# Tic_Tac_Toe_2_0.net
KiCad netlist of a schematic drawn in EAGLE
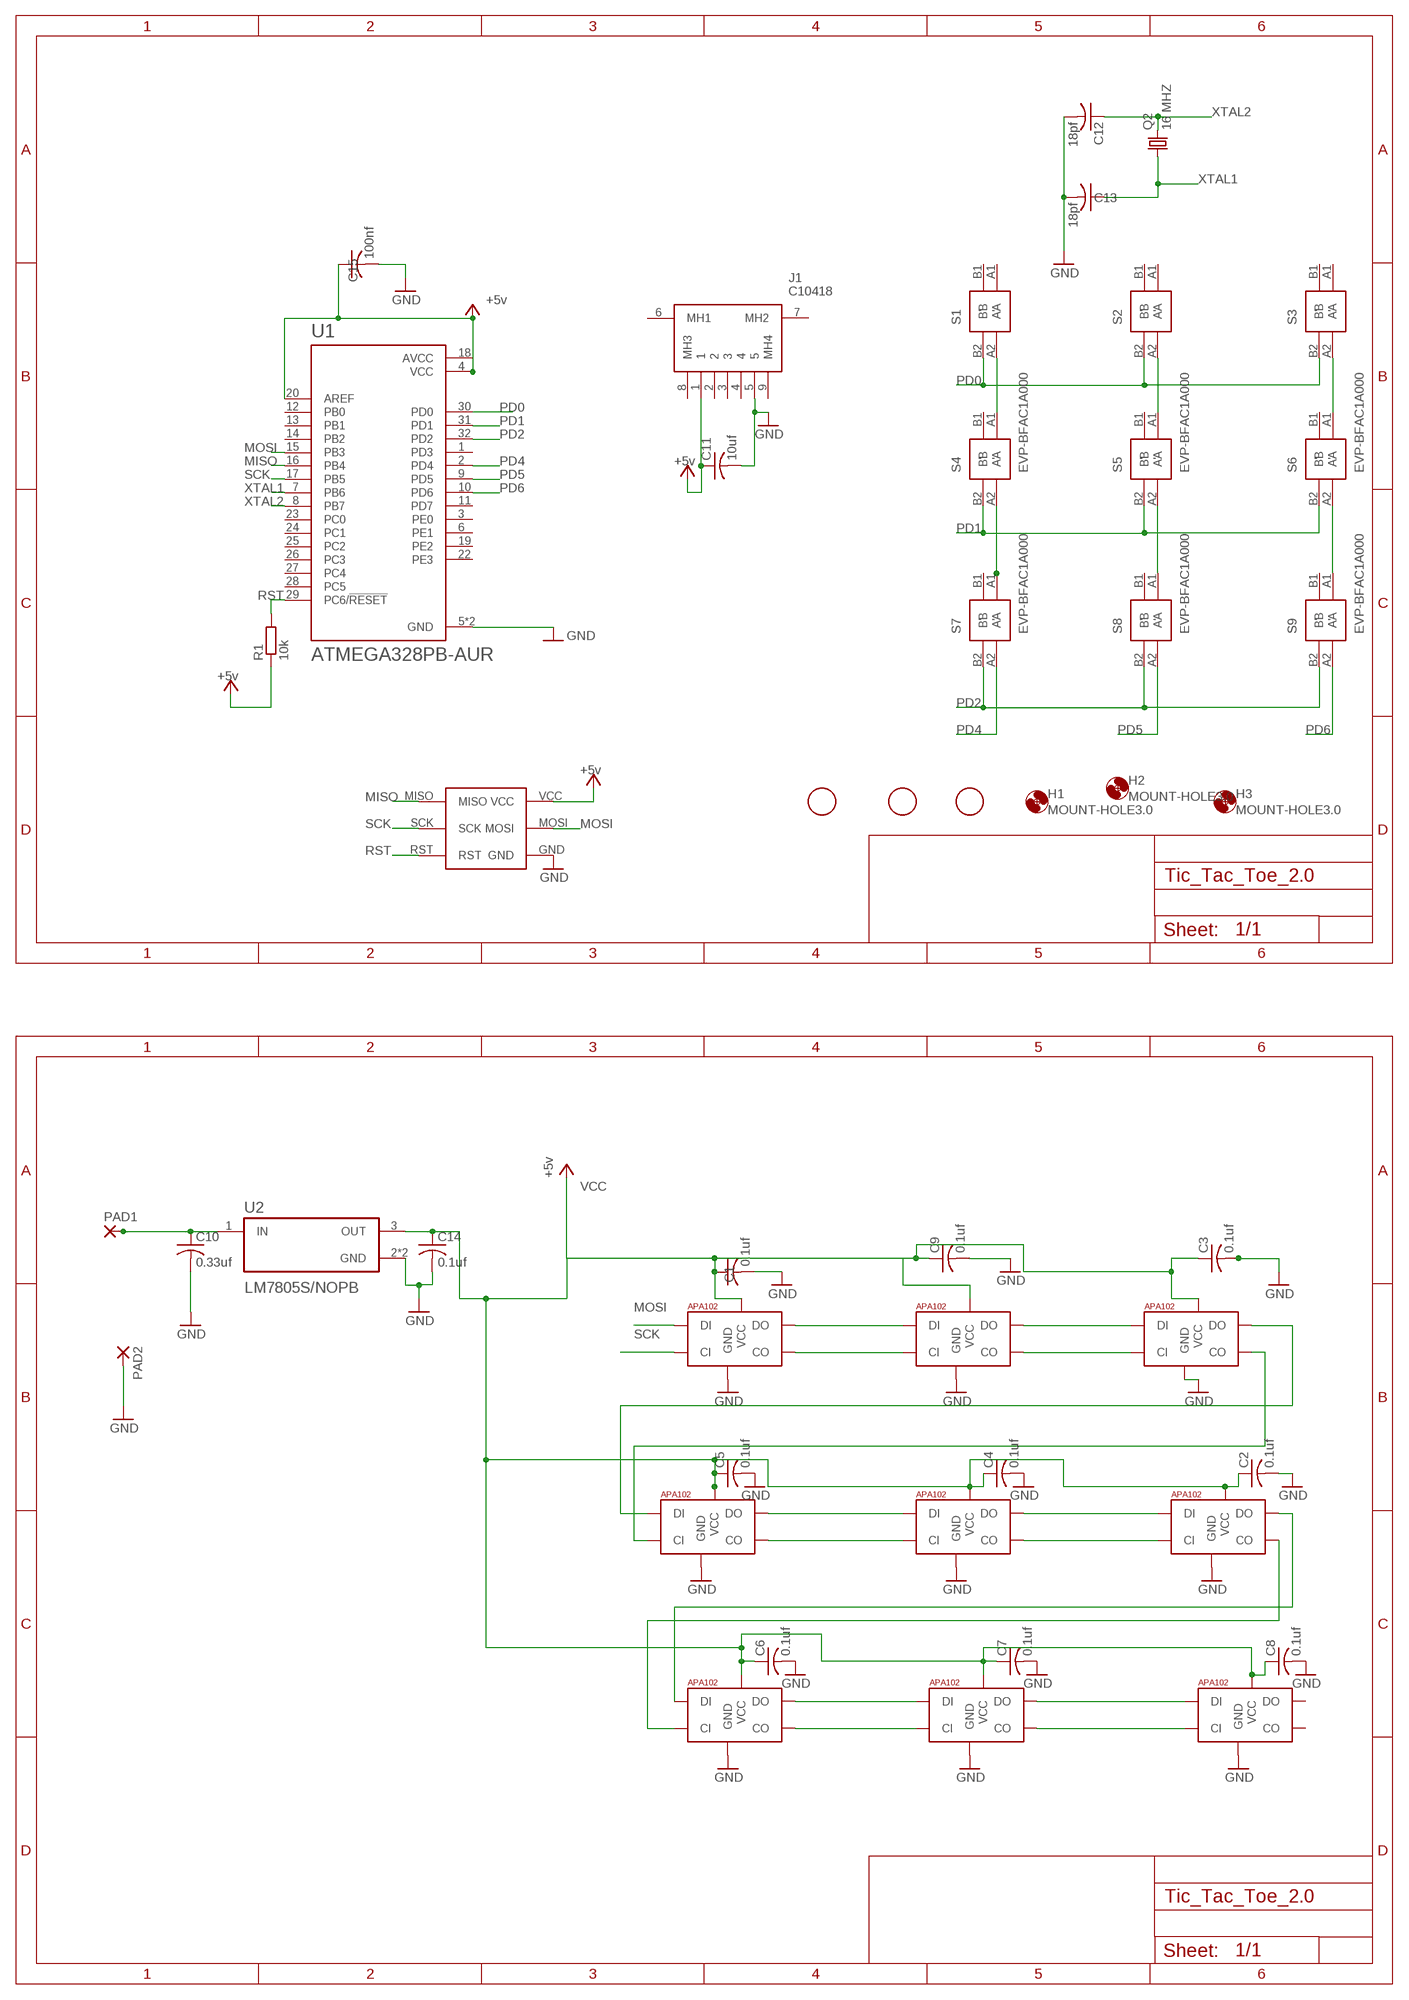
[diagram p0: schematic, sheet 1]

(export (version "E")
  (design (tool "Eeschema 10.0.6"))
  (components
    (comp (ref "C1")
      (value "0.1uf")
      (footprint "eagle-import:C0805")
      (libsource (lib "eagle-import") (part "C-USC0805"))
    )
    (comp (ref "C2")
      (value "0.1uf")
      (footprint "eagle-import:C0805")
      (libsource (lib "eagle-import") (part "C-USC0805"))
    )
    (comp (ref "C3")
      (value "0.1uf")
      (footprint "eagle-import:C0805")
      (libsource (lib "eagle-import") (part "C-USC0805"))
    )
    (comp (ref "C4")
      (value "0.1uf")
      (footprint "eagle-import:C0805")
      (libsource (lib "eagle-import") (part "C-USC0805"))
    )
    (comp (ref "C5")
      (value "0.1uf")
      (footprint "eagle-import:C0805")
      (libsource (lib "eagle-import") (part "C-USC0805"))
    )
    (comp (ref "C6")
      (value "0.1uf")
      (footprint "eagle-import:C0805")
      (libsource (lib "eagle-import") (part "C-USC0805"))
    )
    (comp (ref "C7")
      (value "0.1uf")
      (footprint "eagle-import:C0805")
      (libsource (lib "eagle-import") (part "C-USC0805"))
    )
    (comp (ref "C8")
      (value "0.1uf")
      (footprint "eagle-import:C0805")
      (libsource (lib "eagle-import") (part "C-USC0805"))
    )
    (comp (ref "C9")
      (value "0.1uf")
      (footprint "eagle-import:C0805")
      (libsource (lib "eagle-import") (part "C-USC0805"))
    )
    (comp (ref "C10")
      (value "0.33uf")
      (footprint "eagle-import:C0805")
      (libsource (lib "eagle-import") (part "C-USC0805"))
    )
    (comp (ref "C11")
      (value "10uf")
      (footprint "eagle-import:C0805")
      (libsource (lib "eagle-import") (part "C-USC0805"))
    )
    (comp (ref "C12")
      (value "18pf")
      (footprint "eagle-import:C0805")
      (libsource (lib "eagle-import") (part "C-USC0805"))
    )
    (comp (ref "C13")
      (value "18pf")
      (footprint "eagle-import:C0805")
      (libsource (lib "eagle-import") (part "C-USC0805"))
    )
    (comp (ref "C14")
      (value "0.1uf")
      (footprint "eagle-import:C0805")
      (libsource (lib "eagle-import") (part "C-USC0805"))
    )
    (comp (ref "C15")
      (value "100nf")
      (footprint "eagle-import:C0805")
      (libsource (lib "eagle-import") (part "C-USC0805"))
    )
    (comp (ref "H1")
      (value "MOUNT-HOLE3.0")
      (footprint "eagle-import:3,0")
      (libsource (lib "eagle-import") (part "MOUNT-HOLE3.0"))
    )
    (comp (ref "H2")
      (value "MOUNT-HOLE3.0")
      (footprint "eagle-import:3,0")
      (libsource (lib "eagle-import") (part "MOUNT-HOLE3.0"))
    )
    (comp (ref "H3")
      (value "MOUNT-HOLE3.0")
      (footprint "eagle-import:3,0")
      (libsource (lib "eagle-import") (part "MOUNT-HOLE3.0"))
    )
    (comp (ref "J1")
      (value "C10418")
      (footprint "eagle-import:C10418")
      (libsource (lib "eagle-import") (part "C10418"))
    )
    (comp (ref "PAD1")
      (value "2,15/1,0")
      (footprint "eagle-import:2,15_1,0")
      (libsource (lib "eagle-import") (part "2,15/1,0"))
    )
    (comp (ref "PAD2")
      (value "2,15/1,0")
      (footprint "eagle-import:2,15_1,0")
      (libsource (lib "eagle-import") (part "2,15/1,0"))
    )
    (comp (ref "Q2")
      (value "16 MHZ")
      (footprint "eagle-import:HC49UP")
      (libsource (lib "eagle-import") (part "CRYSTALHC49UP"))
    )
    (comp (ref "R1")
      (value "10k")
      (footprint "eagle-import:M0805")
      (libsource (lib "eagle-import") (part "R-EU_M0805"))
    )
    (comp (ref "S1")
      (value "EVP-BFAC1A000")
      (footprint "eagle-import:EVPBFAC1A000")
      (fields (field (name "MF") "Panasonic Electronic"))
      (libsource (lib "eagle-import") (part "EVP-BFAC1A000"))
    )
    (comp (ref "S2")
      (value "EVP-BFAC1A000")
      (footprint "eagle-import:EVPBFAC1A000")
      (fields (field (name "MF") "Panasonic Electronic"))
      (libsource (lib "eagle-import") (part "EVP-BFAC1A000"))
    )
    (comp (ref "S3")
      (value "EVP-BFAC1A000")
      (footprint "eagle-import:EVPBFAC1A000")
      (fields (field (name "MF") "Panasonic Electronic"))
      (libsource (lib "eagle-import") (part "EVP-BFAC1A000"))
    )
    (comp (ref "S4")
      (value "EVP-BFAC1A000")
      (footprint "eagle-import:EVPBFAC1A000")
      (fields (field (name "MF") "Panasonic Electronic"))
      (libsource (lib "eagle-import") (part "EVP-BFAC1A000"))
    )
    (comp (ref "S5")
      (value "EVP-BFAC1A000")
      (footprint "eagle-import:EVPBFAC1A000")
      (fields (field (name "MF") "Panasonic Electronic"))
      (libsource (lib "eagle-import") (part "EVP-BFAC1A000"))
    )
    (comp (ref "S6")
      (value "EVP-BFAC1A000")
      (footprint "eagle-import:EVPBFAC1A000")
      (fields (field (name "MF") "Panasonic Electronic"))
      (libsource (lib "eagle-import") (part "EVP-BFAC1A000"))
    )
    (comp (ref "S7")
      (value "EVP-BFAC1A000")
      (footprint "eagle-import:EVPBFAC1A000")
      (fields (field (name "MF") "Panasonic Electronic"))
      (libsource (lib "eagle-import") (part "EVP-BFAC1A000"))
    )
    (comp (ref "S8")
      (value "EVP-BFAC1A000")
      (footprint "eagle-import:EVPBFAC1A000")
      (fields (field (name "MF") "Panasonic Electronic"))
      (libsource (lib "eagle-import") (part "EVP-BFAC1A000"))
    )
    (comp (ref "S9")
      (value "EVP-BFAC1A000")
      (footprint "eagle-import:EVPBFAC1A000")
      (fields (field (name "MF") "Panasonic Electronic"))
      (libsource (lib "eagle-import") (part "EVP-BFAC1A000"))
    )
    (comp (ref "U$1")
      (value "AVR-ISP")
      (footprint "eagle-import:AVR-ISP")
      (fields (field (name "MF") "Gravitech"))
      (libsource (lib "eagle-import") (part "AVR-ISP"))
    )
    (comp (ref "U$2")
      (value "APA1025050")
      (footprint "eagle-import:APA102_5050")
      (libsource (lib "eagle-import") (part "APA1025050"))
    )
    (comp (ref "U$3")
      (value "APA1025050")
      (footprint "eagle-import:APA102_5050")
      (libsource (lib "eagle-import") (part "APA1025050"))
    )
    (comp (ref "U$4")
      (value "APA1025050")
      (footprint "eagle-import:APA102_5050")
      (libsource (lib "eagle-import") (part "APA1025050"))
    )
    (comp (ref "U$5")
      (value "APA1025050")
      (footprint "eagle-import:APA102_5050")
      (libsource (lib "eagle-import") (part "APA1025050"))
    )
    (comp (ref "U$6")
      (value "APA1025050")
      (footprint "eagle-import:APA102_5050")
      (libsource (lib "eagle-import") (part "APA1025050"))
    )
    (comp (ref "U$7")
      (value "APA1025050")
      (footprint "eagle-import:APA102_5050")
      (libsource (lib "eagle-import") (part "APA1025050"))
    )
    (comp (ref "U$8")
      (value "APA1025050")
      (footprint "eagle-import:APA102_5050")
      (libsource (lib "eagle-import") (part "APA1025050"))
    )
    (comp (ref "U$9")
      (value "APA1025050")
      (footprint "eagle-import:APA102_5050")
      (libsource (lib "eagle-import") (part "APA1025050"))
    )
    (comp (ref "U$10")
      (value "APA1025050")
      (footprint "eagle-import:APA102_5050")
      (libsource (lib "eagle-import") (part "APA1025050"))
    )
    (comp (ref "U$11")
      (value "FIDUCIAL")
      (footprint "eagle-import:FIDUCIAL_1MM")
      (libsource (lib "eagle-import") (part "FIDUCIAL"))
    )
    (comp (ref "U$12")
      (value "FIDUCIAL")
      (footprint "eagle-import:FIDUCIAL_1MM")
      (libsource (lib "eagle-import") (part "FIDUCIAL"))
    )
    (comp (ref "U$13")
      (value "FIDUCIAL")
      (footprint "eagle-import:FIDUCIAL_1MM")
      (libsource (lib "eagle-import") (part "FIDUCIAL"))
    )
    (comp (ref "U1")
      (value "ATMEGA328PB-AUR")
      (footprint "eagle-import:QFP80P900X900X120-32N")
      (fields (field (name "DIGI-KEY_PART_NUMBER") "ATMEGA328PB-AURCT-ND") (field (name "MF") "Microchip"))
      (libsource (lib "eagle-import") (part "ATMEGA328PB-AUR"))
    )
    (comp (ref "U2")
      (value "LM7805S/NOPB")
      (footprint "eagle-import:TO254P1524X483-4N")
      (fields (field (name "MF") "Texas Instruments"))
      (libsource (lib "eagle-import") (part "LM7805S/NOPB"))
    )
  )
  (nets
    (net (code "1") (name "+5v") (class "Default")
      (node (ref "C1") (pin "1") (pinfunction "1_1") (pintype "passive"))
      (node (ref "C11") (pin "1") (pinfunction "1_1") (pintype "passive"))
      (node (ref "C14") (pin "1") (pinfunction "1_1") (pintype "passive"))
      (node (ref "C15") (pin "1") (pinfunction "1_1") (pintype "passive"))
      (node (ref "C2") (pin "1") (pinfunction "1_1") (pintype "passive"))
      (node (ref "C3") (pin "1") (pinfunction "1_1") (pintype "passive"))
      (node (ref "C4") (pin "1") (pinfunction "1_1") (pintype "passive"))
      (node (ref "C5") (pin "1") (pinfunction "1_1") (pintype "passive"))
      (node (ref "C6") (pin "1") (pinfunction "1_1") (pintype "passive"))
      (node (ref "C7") (pin "1") (pinfunction "1_1") (pintype "passive"))
      (node (ref "C8") (pin "1") (pinfunction "1_1") (pintype "passive"))
      (node (ref "C9") (pin "1") (pinfunction "1_1") (pintype "passive"))
      (node (ref "J1") (pin "1") (pinfunction "1_1") (pintype "bidirectional"))
      (node (ref "R1") (pin "1") (pinfunction "1_1") (pintype "passive"))
      (node (ref "U$1") (pin "VCC") (pinfunction "VCC_VCC") (pintype "bidirectional"))
      (node (ref "U$10") (pin "1") (pinfunction "VCC_1") (pintype "bidirectional"))
      (node (ref "U$2") (pin "1") (pinfunction "VCC_1") (pintype "bidirectional"))
      (node (ref "U$3") (pin "1") (pinfunction "VCC_1") (pintype "bidirectional"))
      (node (ref "U$4") (pin "1") (pinfunction "VCC_1") (pintype "bidirectional"))
      (node (ref "U$5") (pin "1") (pinfunction "VCC_1") (pintype "bidirectional"))
      (node (ref "U$6") (pin "1") (pinfunction "VCC_1") (pintype "bidirectional"))
      (node (ref "U$7") (pin "1") (pinfunction "VCC_1") (pintype "bidirectional"))
      (node (ref "U$8") (pin "1") (pinfunction "VCC_1") (pintype "bidirectional"))
      (node (ref "U$9") (pin "1") (pinfunction "VCC_1") (pintype "bidirectional"))
      (node (ref "U1") (pin "18") (pinfunction "AVCC_18") (pintype "power_in"))
      (node (ref "U1") (pin "20") (pinfunction "AREF_20") (pintype "input"))
      (node (ref "U1") (pin "4") (pinfunction "VCC_4") (pintype "power_in"))
      (node (ref "U2") (pin "3") (pinfunction "OUT_3") (pintype "output"))
    )
    (net (code "2") (name "/MISO") (class "Default")
      (node (ref "U$1") (pin "MISO") (pinfunction "MISO_MISO") (pintype "bidirectional"))
      (node (ref "U1") (pin "16") (pinfunction "PB4_16") (pintype "bidirectional"))
    )
    (net (code "3") (name "/MOSI") (class "Default")
      (node (ref "U$1") (pin "MOSI") (pinfunction "MOSI_MOSI") (pintype "bidirectional"))
      (node (ref "U$2") (pin "4") (pinfunction "DI_4") (pintype "bidirectional"))
      (node (ref "U1") (pin "15") (pinfunction "PB3_15") (pintype "bidirectional"))
    )
    (net (code "4") (name "/PD0") (class "Default")
      (node (ref "S1") (pin "B2") (pinfunction "B'_B2") (pintype "bidirectional"))
      (node (ref "S2") (pin "B2") (pinfunction "B'_B2") (pintype "bidirectional"))
      (node (ref "S3") (pin "B2") (pinfunction "B'_B2") (pintype "bidirectional"))
      (node (ref "U1") (pin "30") (pinfunction "PD0_30") (pintype "bidirectional"))
    )
    (net (code "5") (name "/PD1") (class "Default")
      (node (ref "S4") (pin "B2") (pinfunction "B'_B2") (pintype "bidirectional"))
      (node (ref "S5") (pin "B2") (pinfunction "B'_B2") (pintype "bidirectional"))
      (node (ref "S6") (pin "B2") (pinfunction "B'_B2") (pintype "bidirectional"))
      (node (ref "U1") (pin "31") (pinfunction "PD1_31") (pintype "bidirectional"))
    )
    (net (code "6") (name "/PD2") (class "Default")
      (node (ref "S7") (pin "B2") (pinfunction "B'_B2") (pintype "bidirectional"))
      (node (ref "S8") (pin "B2") (pinfunction "B'_B2") (pintype "bidirectional"))
      (node (ref "S9") (pin "B2") (pinfunction "B'_B2") (pintype "bidirectional"))
      (node (ref "U1") (pin "32") (pinfunction "PD2_32") (pintype "bidirectional"))
    )
    (net (code "7") (name "/PD4") (class "Default")
      (node (ref "S7") (pin "A2") (pinfunction "A'_A2") (pintype "bidirectional"))
      (node (ref "U1") (pin "2") (pinfunction "PD4_2") (pintype "bidirectional"))
    )
    (net (code "8") (name "/PD5") (class "Default")
      (node (ref "S8") (pin "A2") (pinfunction "A'_A2") (pintype "bidirectional"))
      (node (ref "U1") (pin "9") (pinfunction "PD5_9") (pintype "bidirectional"))
    )
    (net (code "9") (name "/PD6") (class "Default")
      (node (ref "S9") (pin "A2") (pinfunction "A'_A2") (pintype "bidirectional"))
      (node (ref "U1") (pin "10") (pinfunction "PD6_10") (pintype "bidirectional"))
    )
    (net (code "10") (name "/RST") (class "Default")
      (node (ref "R1") (pin "2") (pinfunction "2_2") (pintype "passive"))
      (node (ref "U$1") (pin "RST") (pinfunction "RST_RST") (pintype "bidirectional"))
      (node (ref "U1") (pin "29") (pinfunction "PC6/~{RESET}_29") (pintype "bidirectional"))
    )
    (net (code "11") (name "/SCK") (class "Default")
      (node (ref "U$1") (pin "SCK") (pinfunction "SCK_SCK") (pintype "bidirectional"))
      (node (ref "U$2") (pin "5") (pinfunction "CI_5") (pintype "bidirectional"))
      (node (ref "U1") (pin "17") (pinfunction "PB5_17") (pintype "bidirectional"))
    )
    (net (code "12") (name "/XTAL1") (class "Default")
      (node (ref "C13") (pin "1") (pinfunction "1_1") (pintype "passive"))
      (node (ref "Q2") (pin "1") (pinfunction "1_1") (pintype "passive"))
      (node (ref "U1") (pin "7") (pinfunction "PB6_7") (pintype "bidirectional"))
    )
    (net (code "13") (name "/XTAL2") (class "Default")
      (node (ref "C12") (pin "1") (pinfunction "1_1") (pintype "passive"))
      (node (ref "Q2") (pin "2") (pinfunction "2_2") (pintype "passive"))
      (node (ref "U1") (pin "8") (pinfunction "PB7_8") (pintype "bidirectional"))
    )
    (net (code "14") (name "GND") (class "Default")
      (node (ref "C1") (pin "2") (pinfunction "2_2") (pintype "passive"))
      (node (ref "C10") (pin "2") (pinfunction "2_2") (pintype "passive"))
      (node (ref "C11") (pin "2") (pinfunction "2_2") (pintype "passive"))
      (node (ref "C12") (pin "2") (pinfunction "2_2") (pintype "passive"))
      (node (ref "C13") (pin "2") (pinfunction "2_2") (pintype "passive"))
      (node (ref "C14") (pin "2") (pinfunction "2_2") (pintype "passive"))
      (node (ref "C15") (pin "2") (pinfunction "2_2") (pintype "passive"))
      (node (ref "C2") (pin "2") (pinfunction "2_2") (pintype "passive"))
      (node (ref "C3") (pin "2") (pinfunction "2_2") (pintype "passive"))
      (node (ref "C4") (pin "2") (pinfunction "2_2") (pintype "passive"))
      (node (ref "C5") (pin "2") (pinfunction "2_2") (pintype "passive"))
      (node (ref "C6") (pin "2") (pinfunction "2_2") (pintype "passive"))
      (node (ref "C7") (pin "2") (pinfunction "2_2") (pintype "passive"))
      (node (ref "C8") (pin "2") (pinfunction "2_2") (pintype "passive"))
      (node (ref "C9") (pin "2") (pinfunction "2_2") (pintype "passive"))
      (node (ref "J1") (pin "5") (pinfunction "5_5") (pintype "bidirectional"))
      (node (ref "PAD2") (pin "1") (pinfunction "P_1") (pintype "passive"))
      (node (ref "U$1") (pin "GND") (pinfunction "GND_GND") (pintype "bidirectional"))
      (node (ref "U$10") (pin "6") (pinfunction "GND_6") (pintype "bidirectional"))
      (node (ref "U$2") (pin "6") (pinfunction "GND_6") (pintype "bidirectional"))
      (node (ref "U$3") (pin "6") (pinfunction "GND_6") (pintype "bidirectional"))
      (node (ref "U$4") (pin "6") (pinfunction "GND_6") (pintype "bidirectional"))
      (node (ref "U$5") (pin "6") (pinfunction "GND_6") (pintype "bidirectional"))
      (node (ref "U$6") (pin "6") (pinfunction "GND_6") (pintype "bidirectional"))
      (node (ref "U$7") (pin "6") (pinfunction "GND_6") (pintype "bidirectional"))
      (node (ref "U$8") (pin "6") (pinfunction "GND_6") (pintype "bidirectional"))
      (node (ref "U$9") (pin "6") (pinfunction "GND_6") (pintype "bidirectional"))
      (node (ref "U1") (pin "21") (pinfunction "GND_21") (pintype "power_in"))
      (node (ref "U1") (pin "5") (pinfunction "GND_5") (pintype "power_in"))
      (node (ref "U2") (pin "2") (pinfunction "GND_2") (pintype "power_in"))
      (node (ref "U2") (pin "4") (pinfunction "GND_4") (pintype "power_in"))
    )
    (net (code "15") (name "Net-(PAD1-P)") (class "Default")
      (node (ref "C10") (pin "1") (pinfunction "1_1") (pintype "passive"))
      (node (ref "PAD1") (pin "1") (pinfunction "P_1") (pintype "passive"))
      (node (ref "U2") (pin "1") (pinfunction "IN_1") (pintype "input"))
    )
    (net (code "16") (name "Net-(S1-A')") (class "Default")
      (node (ref "S1") (pin "A2") (pinfunction "A'_A2") (pintype "bidirectional"))
      (node (ref "S4") (pin "A1") (pinfunction "A_A1") (pintype "bidirectional"))
    )
    (net (code "17") (name "Net-(S2-A')") (class "Default")
      (node (ref "S2") (pin "A2") (pinfunction "A'_A2") (pintype "bidirectional"))
      (node (ref "S5") (pin "A1") (pinfunction "A_A1") (pintype "bidirectional"))
    )
    (net (code "18") (name "Net-(S3-A')") (class "Default")
      (node (ref "S3") (pin "A2") (pinfunction "A'_A2") (pintype "bidirectional"))
      (node (ref "S6") (pin "A1") (pinfunction "A_A1") (pintype "bidirectional"))
    )
    (net (code "19") (name "Net-(S4-A')") (class "Default")
      (node (ref "S4") (pin "A2") (pinfunction "A'_A2") (pintype "bidirectional"))
      (node (ref "S7") (pin "A1") (pinfunction "A_A1") (pintype "bidirectional"))
    )
    (net (code "20") (name "Net-(S5-A')") (class "Default")
      (node (ref "S5") (pin "A2") (pinfunction "A'_A2") (pintype "bidirectional"))
      (node (ref "S8") (pin "A1") (pinfunction "A_A1") (pintype "bidirectional"))
    )
    (net (code "21") (name "Net-(S6-A')") (class "Default")
      (node (ref "S6") (pin "A2") (pinfunction "A'_A2") (pintype "bidirectional"))
      (node (ref "S9") (pin "A1") (pinfunction "A_A1") (pintype "bidirectional"))
    )
    (net (code "22") (name "Net-(U$2-CO)") (class "Default")
      (node (ref "U$2") (pin "2") (pinfunction "CO_2") (pintype "bidirectional"))
      (node (ref "U$3") (pin "5") (pinfunction "CI_5") (pintype "bidirectional"))
    )
    (net (code "23") (name "Net-(U$2-DO)") (class "Default")
      (node (ref "U$2") (pin "3") (pinfunction "DO_3") (pintype "bidirectional"))
      (node (ref "U$3") (pin "4") (pinfunction "DI_4") (pintype "bidirectional"))
    )
    (net (code "24") (name "Net-(U$3-CO)") (class "Default")
      (node (ref "U$3") (pin "2") (pinfunction "CO_2") (pintype "bidirectional"))
      (node (ref "U$4") (pin "5") (pinfunction "CI_5") (pintype "bidirectional"))
    )
    (net (code "25") (name "Net-(U$3-DO)") (class "Default")
      (node (ref "U$3") (pin "3") (pinfunction "DO_3") (pintype "bidirectional"))
      (node (ref "U$4") (pin "4") (pinfunction "DI_4") (pintype "bidirectional"))
    )
    (net (code "26") (name "Net-(U$4-CO)") (class "Default")
      (node (ref "U$4") (pin "2") (pinfunction "CO_2") (pintype "bidirectional"))
      (node (ref "U$5") (pin "5") (pinfunction "CI_5") (pintype "bidirectional"))
    )
    (net (code "27") (name "Net-(U$4-DO)") (class "Default")
      (node (ref "U$4") (pin "3") (pinfunction "DO_3") (pintype "bidirectional"))
      (node (ref "U$5") (pin "4") (pinfunction "DI_4") (pintype "bidirectional"))
    )
    (net (code "28") (name "Net-(U$5-CO)") (class "Default")
      (node (ref "U$5") (pin "2") (pinfunction "CO_2") (pintype "bidirectional"))
      (node (ref "U$6") (pin "5") (pinfunction "CI_5") (pintype "bidirectional"))
    )
    (net (code "29") (name "Net-(U$5-DO)") (class "Default")
      (node (ref "U$5") (pin "3") (pinfunction "DO_3") (pintype "bidirectional"))
      (node (ref "U$6") (pin "4") (pinfunction "DI_4") (pintype "bidirectional"))
    )
    (net (code "30") (name "Net-(U$6-CO)") (class "Default")
      (node (ref "U$6") (pin "2") (pinfunction "CO_2") (pintype "bidirectional"))
      (node (ref "U$7") (pin "5") (pinfunction "CI_5") (pintype "bidirectional"))
    )
    (net (code "31") (name "Net-(U$6-DO)") (class "Default")
      (node (ref "U$6") (pin "3") (pinfunction "DO_3") (pintype "bidirectional"))
      (node (ref "U$7") (pin "4") (pinfunction "DI_4") (pintype "bidirectional"))
    )
    (net (code "32") (name "Net-(U$7-CO)") (class "Default")
      (node (ref "U$7") (pin "2") (pinfunction "CO_2") (pintype "bidirectional"))
      (node (ref "U$8") (pin "5") (pinfunction "CI_5") (pintype "bidirectional"))
    )
    (net (code "33") (name "Net-(U$7-DO)") (class "Default")
      (node (ref "U$7") (pin "3") (pinfunction "DO_3") (pintype "bidirectional"))
      (node (ref "U$8") (pin "4") (pinfunction "DI_4") (pintype "bidirectional"))
    )
    (net (code "34") (name "Net-(U$8-CO)") (class "Default")
      (node (ref "U$8") (pin "2") (pinfunction "CO_2") (pintype "bidirectional"))
      (node (ref "U$9") (pin "5") (pinfunction "CI_5") (pintype "bidirectional"))
    )
    (net (code "35") (name "Net-(U$8-DO)") (class "Default")
      (node (ref "U$8") (pin "3") (pinfunction "DO_3") (pintype "bidirectional"))
      (node (ref "U$9") (pin "4") (pinfunction "DI_4") (pintype "bidirectional"))
    )
    (net (code "36") (name "Net-(U$10-CI)") (class "Default")
      (node (ref "U$10") (pin "5") (pinfunction "CI_5") (pintype "bidirectional"))
      (node (ref "U$9") (pin "2") (pinfunction "CO_2") (pintype "bidirectional"))
    )
    (net (code "37") (name "Net-(U$10-DI)") (class "Default")
      (node (ref "U$10") (pin "4") (pinfunction "DI_4") (pintype "bidirectional"))
      (node (ref "U$9") (pin "3") (pinfunction "DO_3") (pintype "bidirectional"))
    )
    (net (code "38") (name "unconnected-(J1-MH1-Pad6)") (class "Default")
      (node (ref "J1") (pin "6") (pinfunction "MH1_6") (pintype "bidirectional"))
    )
    (net (code "39") (name "unconnected-(J1-MH2-Pad7)") (class "Default")
      (node (ref "J1") (pin "7") (pinfunction "MH2_7") (pintype "bidirectional"))
    )
    (net (code "40") (name "unconnected-(J1-MH3-Pad8)") (class "Default")
      (node (ref "J1") (pin "8") (pinfunction "MH3_8") (pintype "bidirectional"))
    )
    (net (code "41") (name "unconnected-(J1-MH4-Pad9)") (class "Default")
      (node (ref "J1") (pin "9") (pinfunction "MH4_9") (pintype "bidirectional"))
    )
    (net (code "42") (name "unconnected-(J1-Pad2)") (class "Default")
      (node (ref "J1") (pin "2") (pinfunction "2_2") (pintype "bidirectional"))
    )
    (net (code "43") (name "unconnected-(J1-Pad3)") (class "Default")
      (node (ref "J1") (pin "3") (pinfunction "3_3") (pintype "bidirectional"))
    )
    (net (code "44") (name "unconnected-(J1-Pad4)") (class "Default")
      (node (ref "J1") (pin "4") (pinfunction "4_4") (pintype "bidirectional"))
    )
    (net (code "45") (name "unconnected-(S1-A-PadA1)") (class "Default")
      (node (ref "S1") (pin "A1") (pinfunction "A_A1") (pintype "bidirectional"))
    )
    (net (code "46") (name "unconnected-(S1-B-PadB1)") (class "Default")
      (node (ref "S1") (pin "B1") (pinfunction "B_B1") (pintype "bidirectional"))
    )
    (net (code "47") (name "unconnected-(S2-A-PadA1)") (class "Default")
      (node (ref "S2") (pin "A1") (pinfunction "A_A1") (pintype "bidirectional"))
    )
    (net (code "48") (name "unconnected-(S2-B-PadB1)") (class "Default")
      (node (ref "S2") (pin "B1") (pinfunction "B_B1") (pintype "bidirectional"))
    )
    (net (code "49") (name "unconnected-(S3-A-PadA1)") (class "Default")
      (node (ref "S3") (pin "A1") (pinfunction "A_A1") (pintype "bidirectional"))
    )
    (net (code "50") (name "unconnected-(S3-B-PadB1)") (class "Default")
      (node (ref "S3") (pin "B1") (pinfunction "B_B1") (pintype "bidirectional"))
    )
    (net (code "51") (name "unconnected-(S4-B-PadB1)") (class "Default")
      (node (ref "S4") (pin "B1") (pinfunction "B_B1") (pintype "bidirectional"))
    )
    (net (code "52") (name "unconnected-(S5-B-PadB1)") (class "Default")
      (node (ref "S5") (pin "B1") (pinfunction "B_B1") (pintype "bidirectional"))
    )
    (net (code "53") (name "unconnected-(S6-B-PadB1)") (class "Default")
      (node (ref "S6") (pin "B1") (pinfunction "B_B1") (pintype "bidirectional"))
    )
    (net (code "54") (name "unconnected-(S7-B-PadB1)") (class "Default")
      (node (ref "S7") (pin "B1") (pinfunction "B_B1") (pintype "bidirectional"))
    )
    (net (code "55") (name "unconnected-(S8-B-PadB1)") (class "Default")
      (node (ref "S8") (pin "B1") (pinfunction "B_B1") (pintype "bidirectional"))
    )
    (net (code "56") (name "unconnected-(S9-B-PadB1)") (class "Default")
      (node (ref "S9") (pin "B1") (pinfunction "B_B1") (pintype "bidirectional"))
    )
    (net (code "57") (name "unconnected-(U$10-CO-Pad2)") (class "Default")
      (node (ref "U$10") (pin "2") (pinfunction "CO_2") (pintype "bidirectional"))
    )
    (net (code "58") (name "unconnected-(U$10-DO-Pad3)") (class "Default")
      (node (ref "U$10") (pin "3") (pinfunction "DO_3") (pintype "bidirectional"))
    )
    (net (code "59") (name "unconnected-(U1-PB0-Pad12)") (class "Default")
      (node (ref "U1") (pin "12") (pinfunction "PB0_12") (pintype "bidirectional"))
    )
    (net (code "60") (name "unconnected-(U1-PB1-Pad13)") (class "Default")
      (node (ref "U1") (pin "13") (pinfunction "PB1_13") (pintype "bidirectional"))
    )
    (net (code "61") (name "unconnected-(U1-PB2-Pad14)") (class "Default")
      (node (ref "U1") (pin "14") (pinfunction "PB2_14") (pintype "bidirectional"))
    )
    (net (code "62") (name "unconnected-(U1-PC0-Pad23)") (class "Default")
      (node (ref "U1") (pin "23") (pinfunction "PC0_23") (pintype "bidirectional"))
    )
    (net (code "63") (name "unconnected-(U1-PC1-Pad24)") (class "Default")
      (node (ref "U1") (pin "24") (pinfunction "PC1_24") (pintype "bidirectional"))
    )
    (net (code "64") (name "unconnected-(U1-PC2-Pad25)") (class "Default")
      (node (ref "U1") (pin "25") (pinfunction "PC2_25") (pintype "bidirectional"))
    )
    (net (code "65") (name "unconnected-(U1-PC3-Pad26)") (class "Default")
      (node (ref "U1") (pin "26") (pinfunction "PC3_26") (pintype "bidirectional"))
    )
    (net (code "66") (name "unconnected-(U1-PC4-Pad27)") (class "Default")
      (node (ref "U1") (pin "27") (pinfunction "PC4_27") (pintype "bidirectional"))
    )
    (net (code "67") (name "unconnected-(U1-PC5-Pad28)") (class "Default")
      (node (ref "U1") (pin "28") (pinfunction "PC5_28") (pintype "bidirectional"))
    )
    (net (code "68") (name "unconnected-(U1-PD3-Pad1)") (class "Default")
      (node (ref "U1") (pin "1") (pinfunction "PD3_1") (pintype "bidirectional"))
    )
    (net (code "69") (name "unconnected-(U1-PD7-Pad11)") (class "Default")
      (node (ref "U1") (pin "11") (pinfunction "PD7_11") (pintype "bidirectional"))
    )
    (net (code "70") (name "unconnected-(U1-PE0-Pad3)") (class "Default")
      (node (ref "U1") (pin "3") (pinfunction "PE0_3") (pintype "bidirectional"))
    )
    (net (code "71") (name "unconnected-(U1-PE1-Pad6)") (class "Default")
      (node (ref "U1") (pin "6") (pinfunction "PE1_6") (pintype "bidirectional"))
    )
    (net (code "72") (name "unconnected-(U1-PE2-Pad19)") (class "Default")
      (node (ref "U1") (pin "19") (pinfunction "PE2_19") (pintype "bidirectional"))
    )
    (net (code "73") (name "unconnected-(U1-PE3-Pad22)") (class "Default")
      (node (ref "U1") (pin "22") (pinfunction "PE3_22") (pintype "bidirectional"))
    )
  )
)
